# schematic.net
KiCad netlist of a schematic drawn in EasyEDA
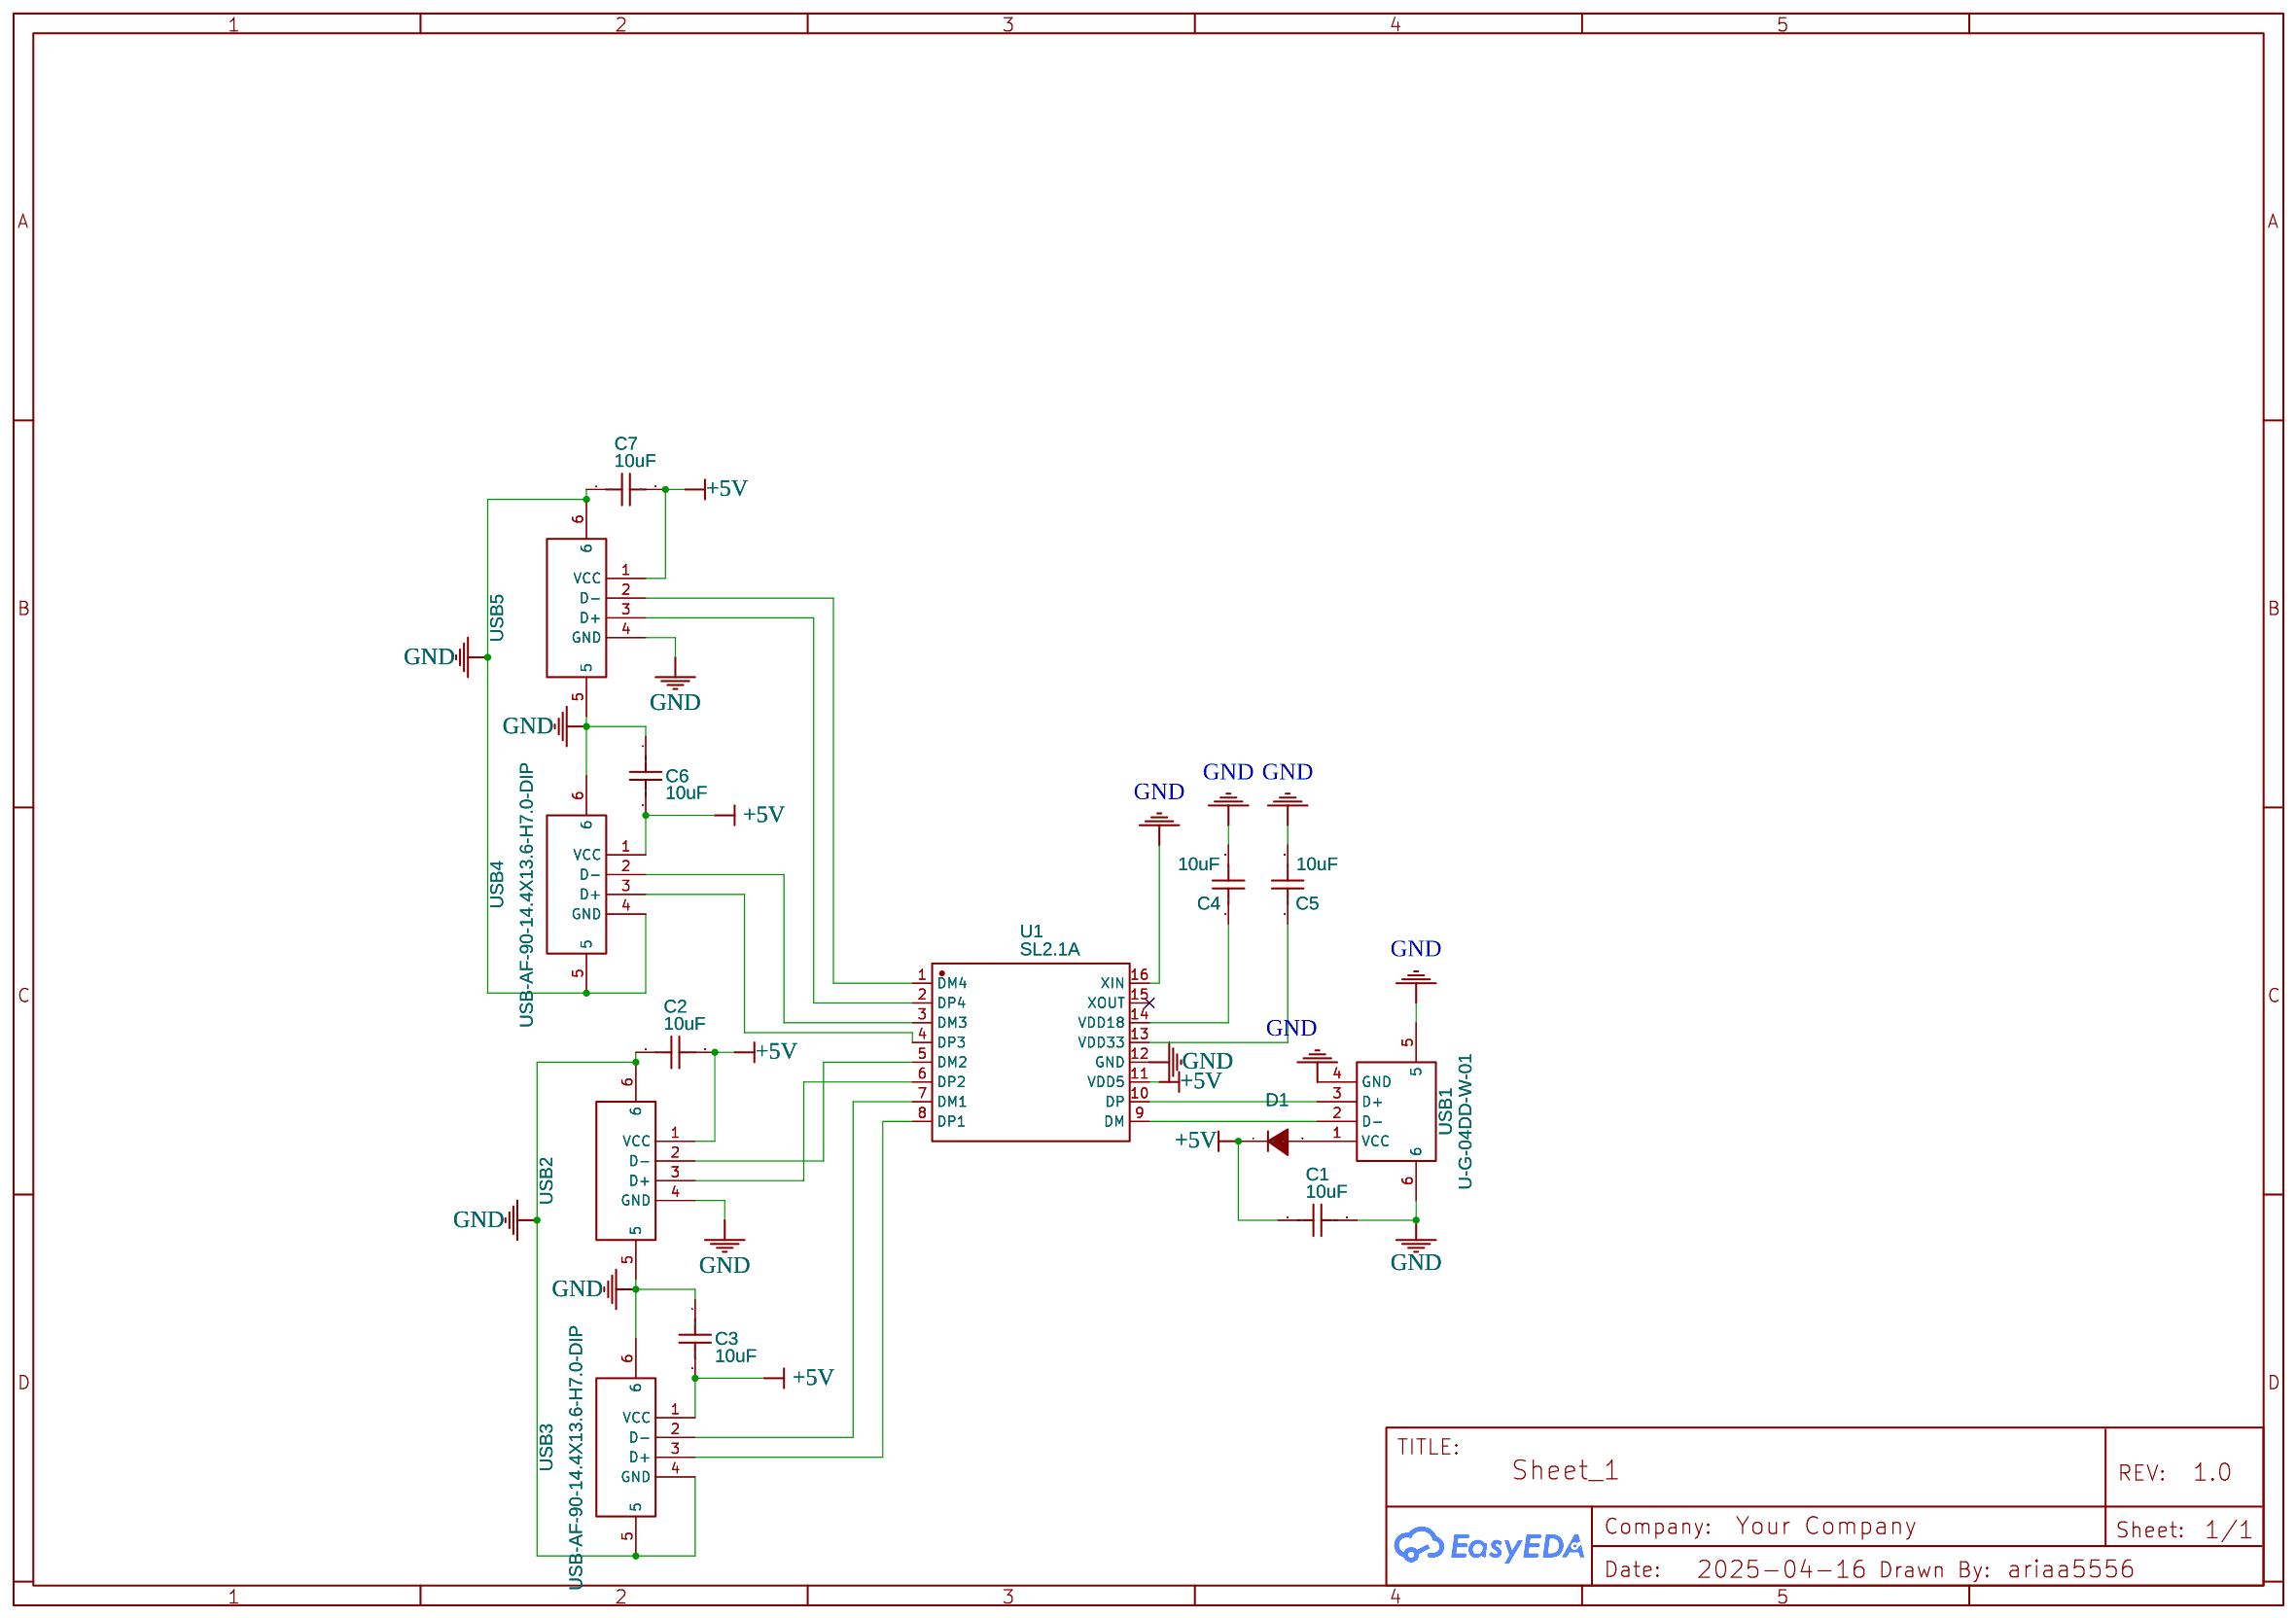
[diagram p0: schematic sheet]

(export (version "E")
  (design (tool "Eeschema 10.0.6"))
  (components
    (comp (ref "C1")
      (value "10uF")
      (fields
        (field (name "Manufacturer Part") "CL10A106KP8NNNC")
        (field (name "Manufacturer") "SAMSUNG(三星)")
      )
      (libsource (lib "") (part "CL10A106KP8NNNC_2"))
    )
    (comp (ref "C2")
      (value "10uF")
      (fields
        (field (name "Manufacturer Part") "CL10A106KP8NNNC")
        (field (name "Manufacturer") "SAMSUNG(三星)")
      )
      (libsource (lib "") (part "CL10A106KP8NNNC_2"))
    )
    (comp (ref "C3")
      (value "10uF")
      (fields
        (field (name "Manufacturer Part") "CL10A106KP8NNNC")
        (field (name "Manufacturer") "SAMSUNG(三星)")
      )
      (libsource (lib "") (part "CL10A106KP8NNNC"))
    )
    (comp (ref "C4")
      (value "10uF")
      (fields
        (field (name "Manufacturer Part") "CL10A106KP8NNNC")
        (field (name "Manufacturer") "SAMSUNG(三星)")
      )
      (libsource (lib "") (part "CL10A106KP8NNNC_1"))
    )
    (comp (ref "C5")
      (value "10uF")
      (fields
        (field (name "Manufacturer Part") "CL10A106KP8NNNC")
        (field (name "Manufacturer") "SAMSUNG(三星)")
      )
      (libsource (lib "") (part "CL10A106KP8NNNC_1"))
    )
    (comp (ref "C6")
      (value "10uF")
      (fields
        (field (name "Manufacturer Part") "CL10A106KP8NNNC")
        (field (name "Manufacturer") "SAMSUNG(三星)")
      )
      (libsource (lib "") (part "CL10A106KP8NNNC"))
    )
    (comp (ref "C7")
      (value "10uF")
      (fields
        (field (name "Manufacturer Part") "CL10A106KP8NNNC")
        (field (name "Manufacturer") "SAMSUNG(三星)")
      )
      (libsource (lib "") (part "CL10A106KP8NNNC_2"))
    )
    (comp (ref "D1")
      (value "NSR0320MW2T1G")
      (fields (field (name "Manufacturer") "onsemi(安森美)"))
      (libsource (lib "") (part "NSR0320MW2T1G"))
    )
    (comp (ref "U1")
      (value "SL2.1A")
      (fields (field (name "Manufacturer") "CoreChips(和芯润德)"))
      (libsource (lib "") (part "SL2.1A"))
    )
    (comp (ref "USB1")
      (value "U-G-04DD-W-01")
      (fields (field (name "Manufacturer Part") "U-G-O4DD-W-1") (field (name "Manufacturer") "韩国韩荣"))
      (libsource (lib "") (part "U-G-04DD-W-01"))
    )
    (comp (ref "USB2")
      (value "USB-AF-90-14.4X13.6-H7.0-DIP")
      (fields (field (name "Manufacturer Part") "903-131A1011D10100") (field (name "Manufacturer") "精拓金"))
      (libsource (lib "") (part "USB-AF-90-14.4X13.6-H7.0-DIP"))
    )
    (comp (ref "USB3")
      (value "USB-AF-90-14.4X13.6-H7.0-DIP")
      (fields (field (name "Manufacturer Part") "903-131A1011D10100") (field (name "Manufacturer") "精拓金"))
      (libsource (lib "") (part "USB-AF-90-14.4X13.6-H7.0-DIP"))
    )
    (comp (ref "USB4")
      (value "USB-AF-90-14.4X13.6-H7.0-DIP")
      (fields (field (name "Manufacturer Part") "903-131A1011D10100") (field (name "Manufacturer") "精拓金"))
      (libsource (lib "") (part "USB-AF-90-14.4X13.6-H7.0-DIP"))
    )
    (comp (ref "USB5")
      (value "USB-AF-90-14.4X13.6-H7.0-DIP")
      (fields (field (name "Manufacturer Part") "903-131A1011D10100") (field (name "Manufacturer") "精拓金"))
      (libsource (lib "") (part "USB-AF-90-14.4X13.6-H7.0-DIP"))
    )
  )
  (nets
    (net (code "1") (name "+5V") (class "Default")
      (node (ref "C1") (pin "1") (pinfunction "1_1") (pintype "unspecified"))
      (node (ref "C2") (pin "2") (pinfunction "2_2") (pintype "unspecified"))
      (node (ref "C3") (pin "2") (pinfunction "2_2") (pintype "unspecified"))
      (node (ref "C6") (pin "2") (pinfunction "2_2") (pintype "unspecified"))
      (node (ref "C7") (pin "2") (pinfunction "2_2") (pintype "unspecified"))
      (node (ref "D1") (pin "1") (pinfunction "C_1") (pintype "unspecified"))
      (node (ref "U1") (pin "11") (pinfunction "VDD5_11") (pintype "unspecified"))
      (node (ref "USB2") (pin "1") (pinfunction "VCC_1") (pintype "unspecified"))
      (node (ref "USB3") (pin "1") (pinfunction "VCC_1") (pintype "unspecified"))
      (node (ref "USB4") (pin "1") (pinfunction "VCC_1") (pintype "unspecified"))
      (node (ref "USB5") (pin "1") (pinfunction "VCC_1") (pintype "unspecified"))
    )
    (net (code "2") (name "GND") (class "Default")
      (node (ref "C1") (pin "2") (pinfunction "2_2") (pintype "unspecified"))
      (node (ref "C2") (pin "1") (pinfunction "1_1") (pintype "unspecified"))
      (node (ref "C3") (pin "1") (pinfunction "1_1") (pintype "unspecified"))
      (node (ref "C4") (pin "2") (pinfunction "2_2") (pintype "unspecified"))
      (node (ref "C5") (pin "2") (pinfunction "2_2") (pintype "unspecified"))
      (node (ref "C6") (pin "1") (pinfunction "1_1") (pintype "unspecified"))
      (node (ref "C7") (pin "1") (pinfunction "1_1") (pintype "unspecified"))
      (node (ref "U1") (pin "12") (pinfunction "GND_12") (pintype "unspecified"))
      (node (ref "U1") (pin "16") (pinfunction "XIN_16") (pintype "unspecified"))
      (node (ref "USB1") (pin "4") (pinfunction "GND_4") (pintype "unspecified"))
      (node (ref "USB1") (pin "5") (pinfunction "5_5") (pintype "unspecified"))
      (node (ref "USB1") (pin "6") (pinfunction "6_6") (pintype "unspecified"))
      (node (ref "USB2") (pin "4") (pinfunction "GND_4") (pintype "unspecified"))
      (node (ref "USB2") (pin "5") (pinfunction "5_5") (pintype "unspecified"))
      (node (ref "USB2") (pin "6") (pinfunction "6_6") (pintype "unspecified"))
      (node (ref "USB3") (pin "4") (pinfunction "GND_4") (pintype "unspecified"))
      (node (ref "USB3") (pin "5") (pinfunction "5_5") (pintype "unspecified"))
      (node (ref "USB3") (pin "6") (pinfunction "6_6") (pintype "unspecified"))
      (node (ref "USB4") (pin "4") (pinfunction "GND_4") (pintype "unspecified"))
      (node (ref "USB4") (pin "5") (pinfunction "5_5") (pintype "unspecified"))
      (node (ref "USB4") (pin "6") (pinfunction "6_6") (pintype "unspecified"))
      (node (ref "USB5") (pin "4") (pinfunction "GND_4") (pintype "unspecified"))
      (node (ref "USB5") (pin "5") (pinfunction "5_5") (pintype "unspecified"))
      (node (ref "USB5") (pin "6") (pinfunction "6_6") (pintype "unspecified"))
    )
    (net (code "3") (name "Net-(D1-A)") (class "Default")
      (node (ref "D1") (pin "2") (pinfunction "A_2") (pintype "unspecified"))
      (node (ref "USB1") (pin "1") (pinfunction "VCC_1") (pintype "unspecified"))
    )
    (net (code "4") (name "Net-(U1-DM)") (class "Default")
      (node (ref "U1") (pin "9") (pinfunction "DM_9") (pintype "unspecified"))
      (node (ref "USB1") (pin "2") (pinfunction "D-_2") (pintype "unspecified"))
    )
    (net (code "5") (name "Net-(U1-DM1)") (class "Default")
      (node (ref "U1") (pin "7") (pinfunction "DM1_7") (pintype "unspecified"))
      (node (ref "USB3") (pin "2") (pinfunction "D-_2") (pintype "unspecified"))
    )
    (net (code "6") (name "Net-(U1-DM2)") (class "Default")
      (node (ref "U1") (pin "5") (pinfunction "DM2_5") (pintype "unspecified"))
      (node (ref "USB2") (pin "2") (pinfunction "D-_2") (pintype "unspecified"))
    )
    (net (code "7") (name "Net-(U1-DM3)") (class "Default")
      (node (ref "U1") (pin "3") (pinfunction "DM3_3") (pintype "unspecified"))
      (node (ref "USB4") (pin "2") (pinfunction "D-_2") (pintype "unspecified"))
    )
    (net (code "8") (name "Net-(U1-DM4)") (class "Default")
      (node (ref "U1") (pin "1") (pinfunction "DM4_1") (pintype "unspecified"))
      (node (ref "USB5") (pin "2") (pinfunction "D-_2") (pintype "unspecified"))
    )
    (net (code "9") (name "Net-(U1-DP)") (class "Default")
      (node (ref "U1") (pin "10") (pinfunction "DP_10") (pintype "unspecified"))
      (node (ref "USB1") (pin "3") (pinfunction "D+_3") (pintype "unspecified"))
    )
    (net (code "10") (name "Net-(U1-DP1)") (class "Default")
      (node (ref "U1") (pin "8") (pinfunction "DP1_8") (pintype "unspecified"))
      (node (ref "USB3") (pin "3") (pinfunction "D+_3") (pintype "unspecified"))
    )
    (net (code "11") (name "Net-(U1-DP2)") (class "Default")
      (node (ref "U1") (pin "6") (pinfunction "DP2_6") (pintype "unspecified"))
      (node (ref "USB2") (pin "3") (pinfunction "D+_3") (pintype "unspecified"))
    )
    (net (code "12") (name "Net-(U1-DP3)") (class "Default")
      (node (ref "U1") (pin "4") (pinfunction "DP3_4") (pintype "unspecified"))
      (node (ref "USB4") (pin "3") (pinfunction "D+_3") (pintype "unspecified"))
    )
    (net (code "13") (name "Net-(U1-DP4)") (class "Default")
      (node (ref "U1") (pin "2") (pinfunction "DP4_2") (pintype "unspecified"))
      (node (ref "USB5") (pin "3") (pinfunction "D+_3") (pintype "unspecified"))
    )
    (net (code "14") (name "Net-(U1-VDD18)") (class "Default")
      (node (ref "C4") (pin "1") (pinfunction "1_1") (pintype "unspecified"))
      (node (ref "U1") (pin "14") (pinfunction "VDD18_14") (pintype "unspecified"))
    )
    (net (code "15") (name "Net-(U1-VDD33)") (class "Default")
      (node (ref "C5") (pin "1") (pinfunction "1_1") (pintype "unspecified"))
      (node (ref "U1") (pin "13") (pinfunction "VDD33_13") (pintype "unspecified"))
    )
    (net (code "16") (name "unconnected-(U1-XOUT-Pad15)") (class "Default")
      (node (ref "U1") (pin "15") (pinfunction "XOUT_15") (pintype "unspecified+no_connect"))
    )
  )
)
